# mainboard.net
KiCad netlist of a schematic drawn in EAGLE
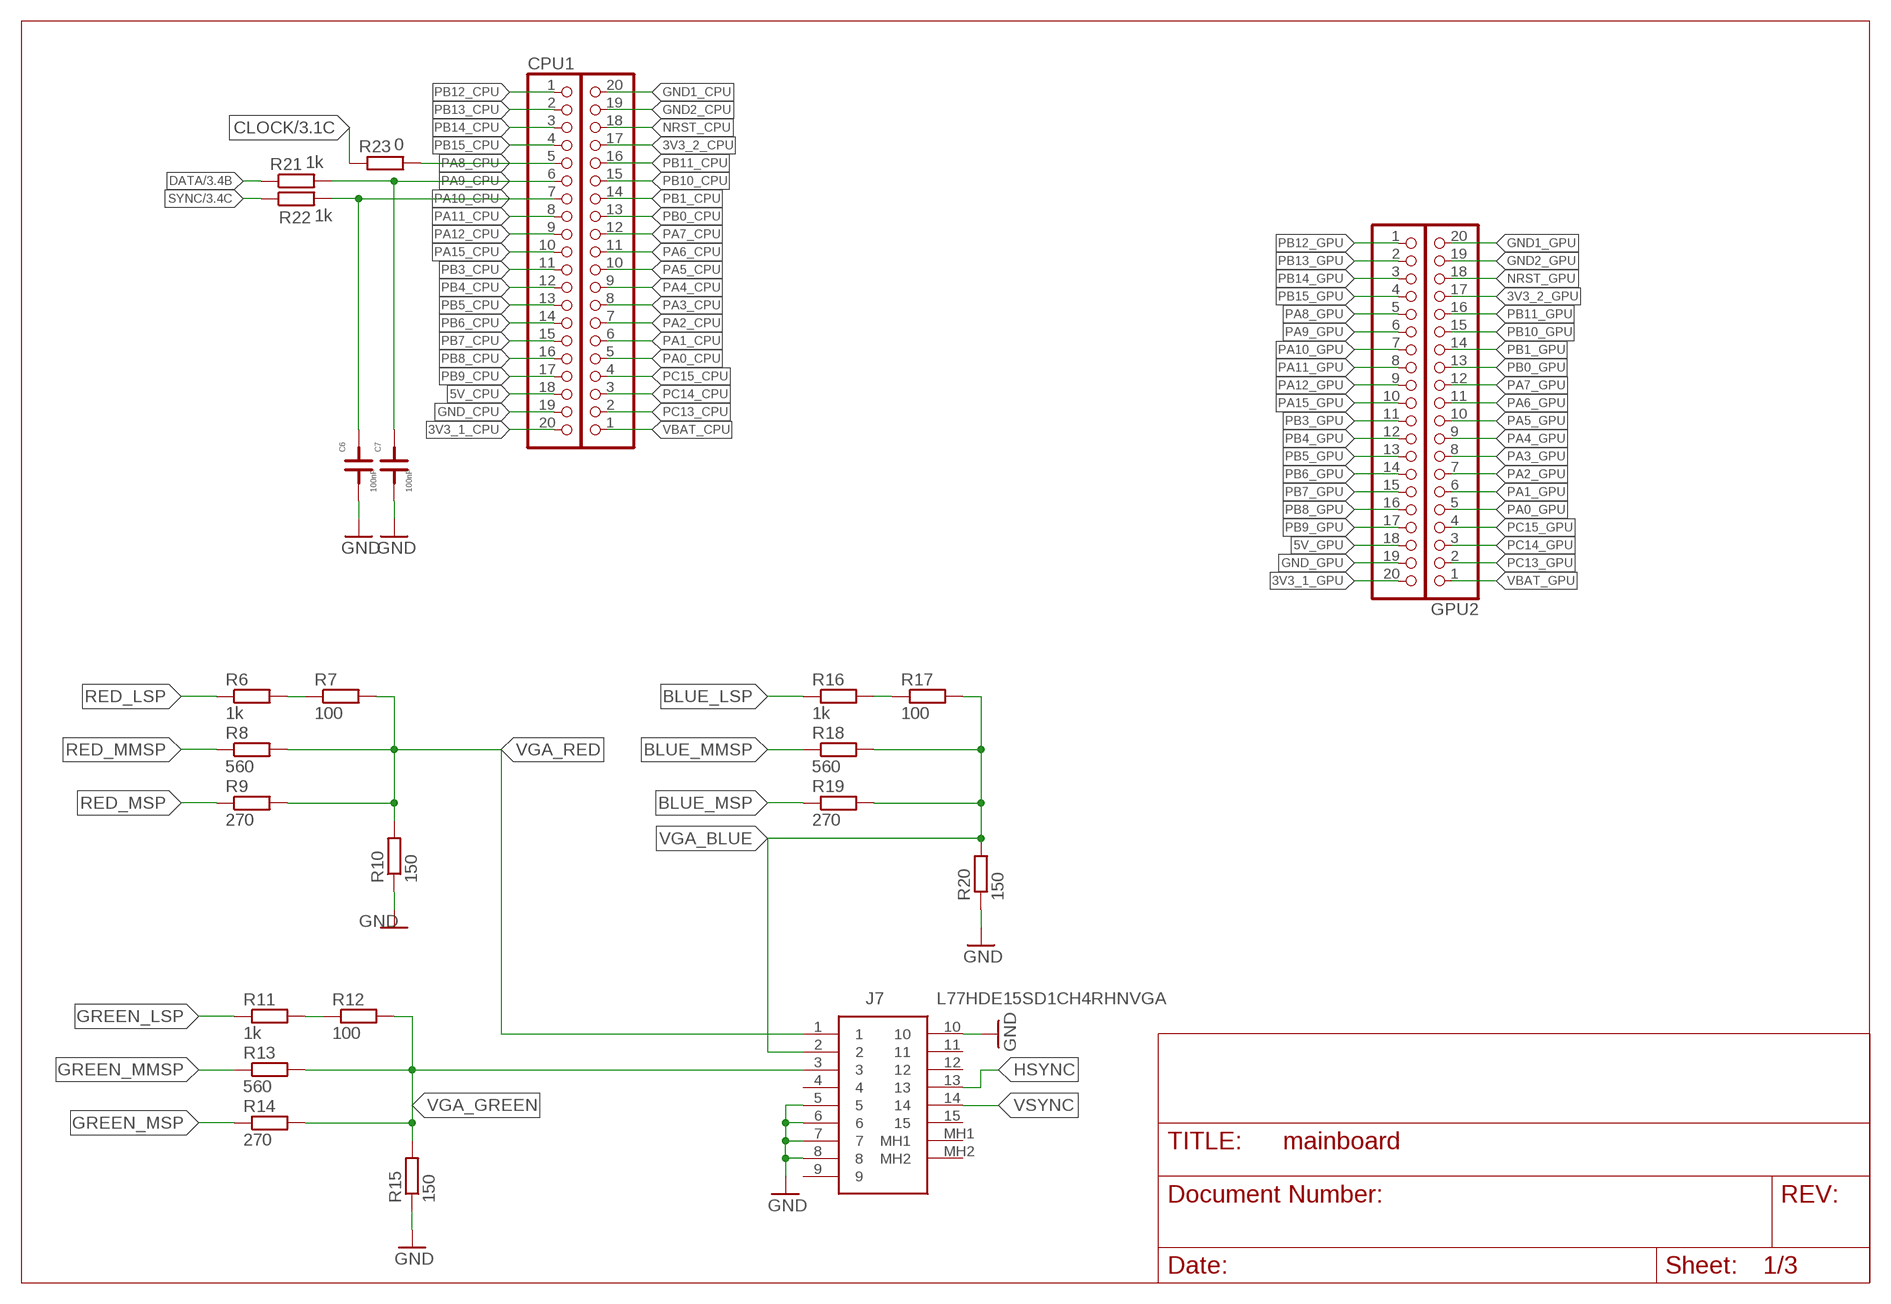
[diagram p0: schematic, sheet 1]
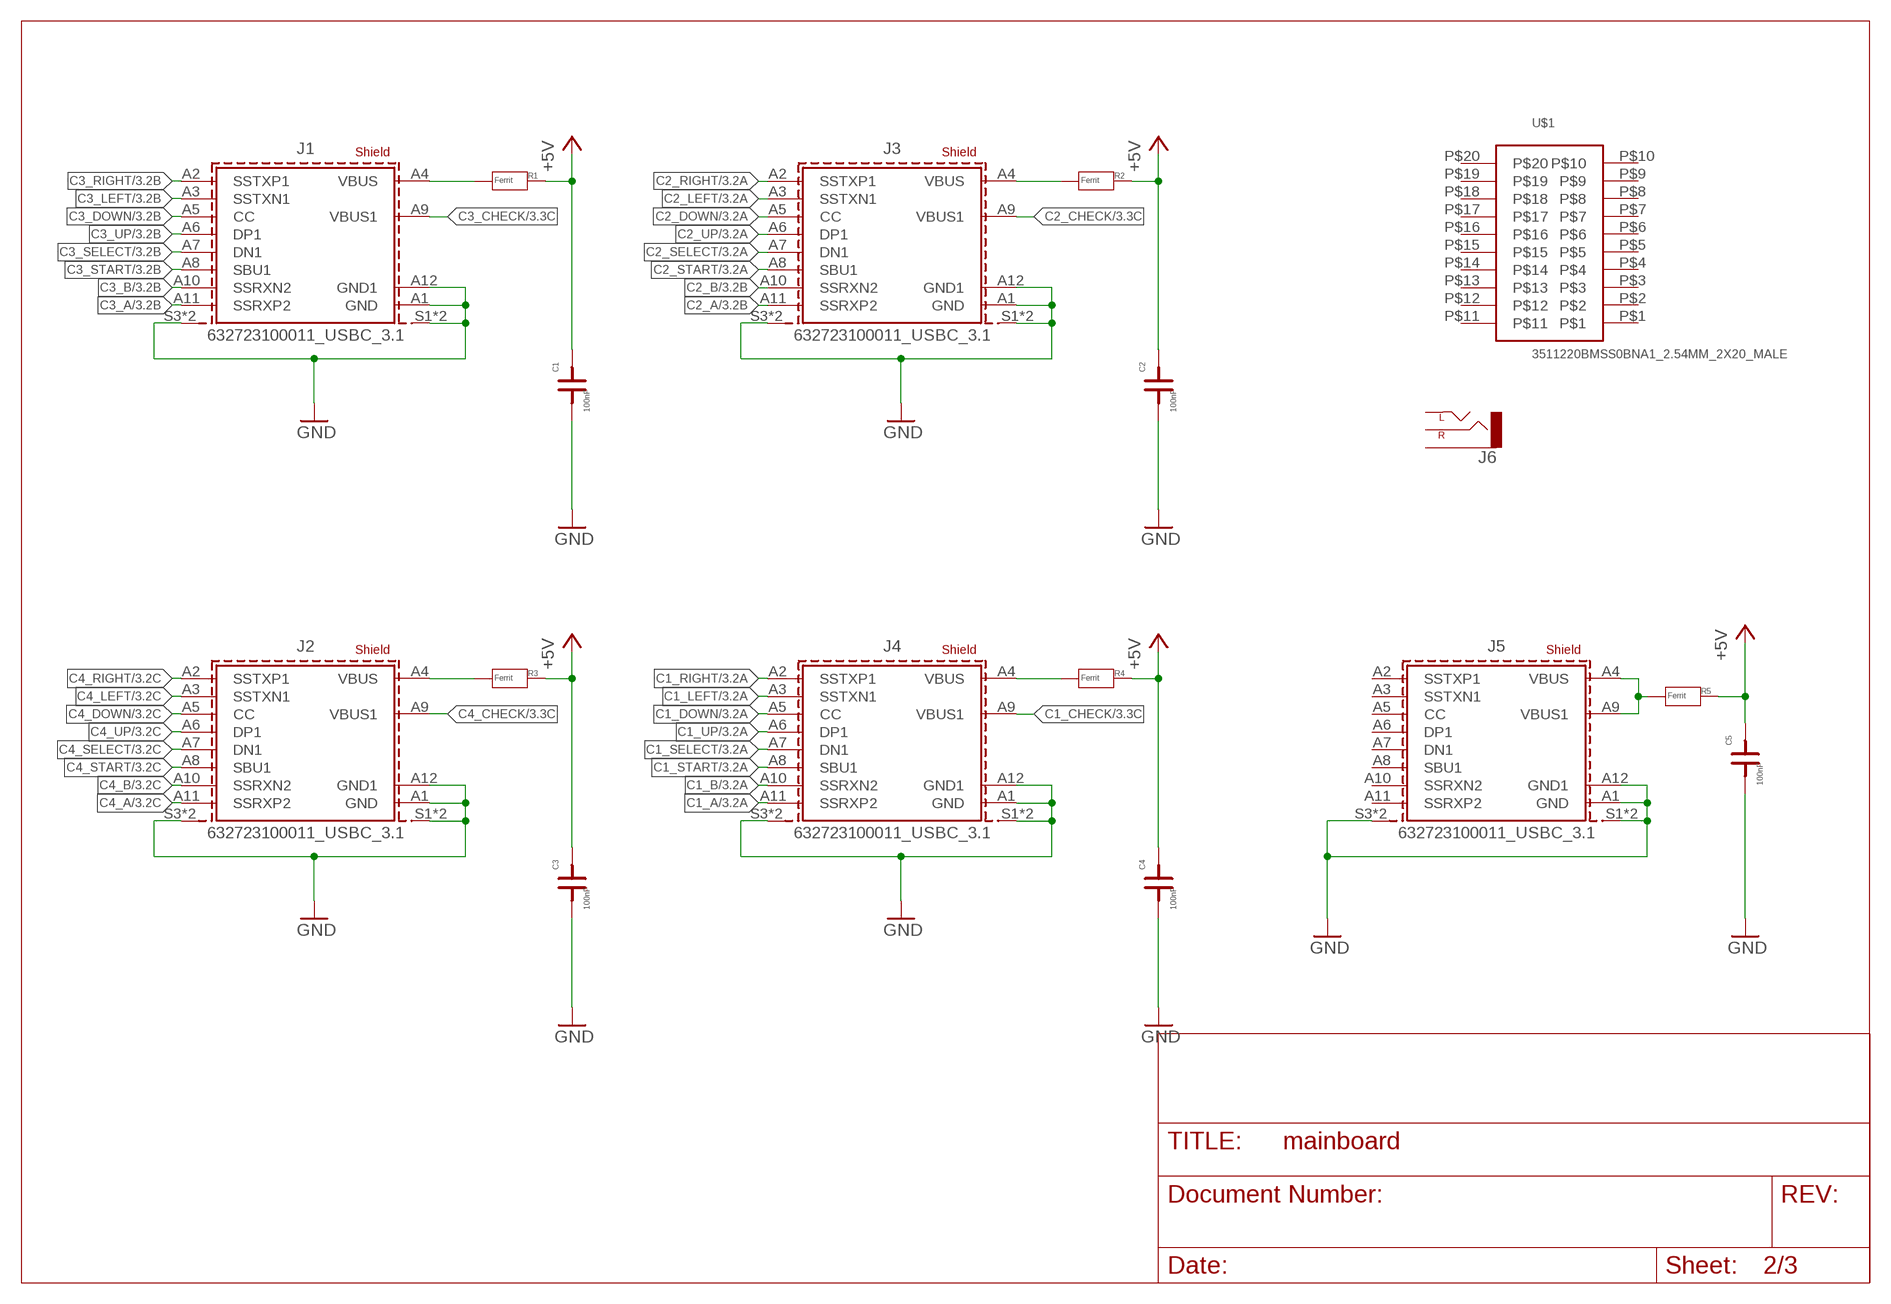
[diagram p1: schematic, sheet 2]
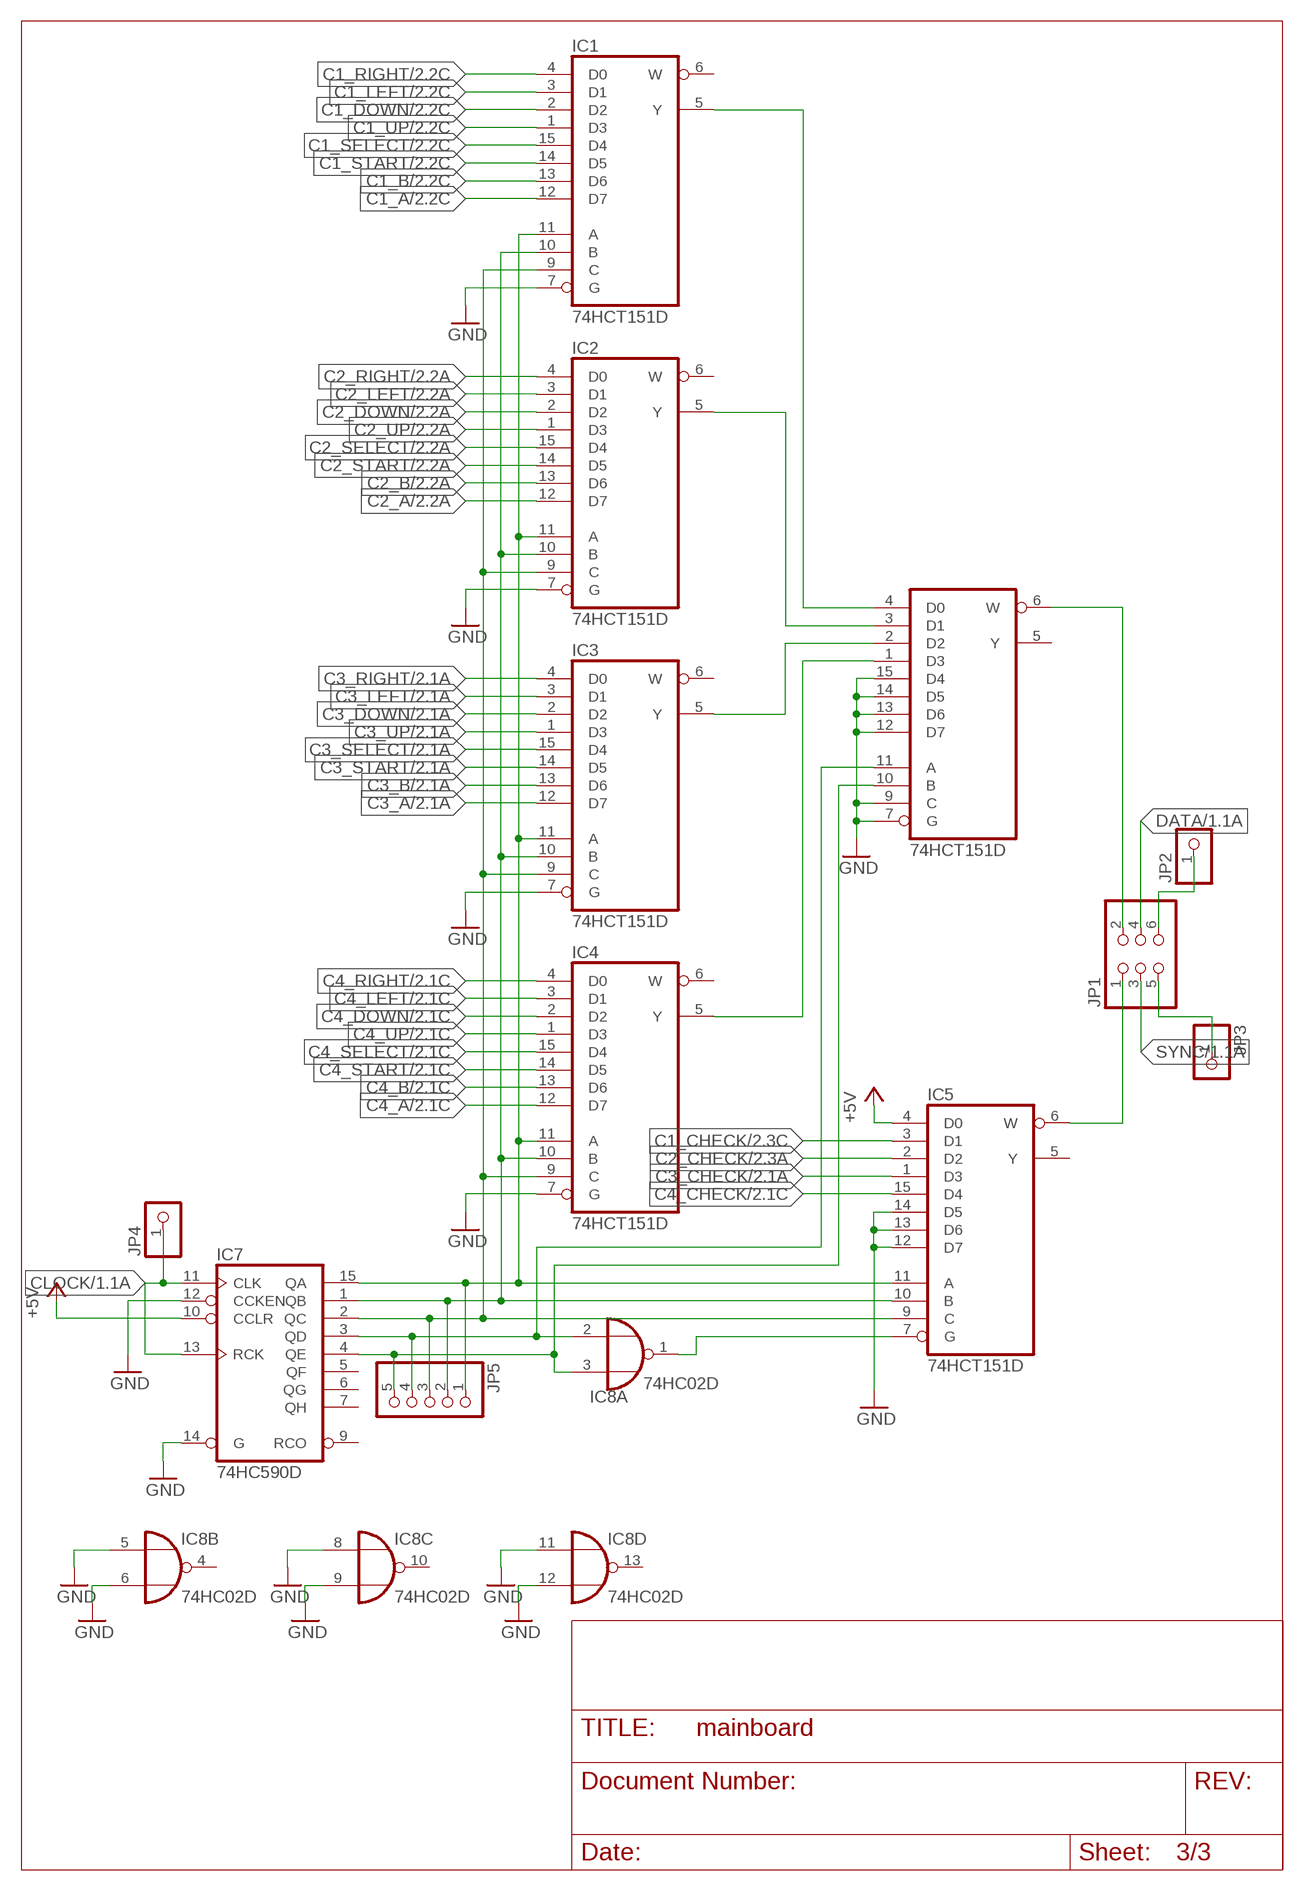
[diagram p2: schematic, sheet 3]

(export (version "E")
  (design (tool "Eeschema 10.0.6"))
  (components
    (comp (ref "C1")
      (value "100nF")
      (footprint "eagle-import:0805F")
      (libsource (lib "eagle-import") (part "C1"))
    )
    (comp (ref "C2")
      (value "100nF")
      (footprint "eagle-import:0805F")
      (libsource (lib "eagle-import") (part "C1"))
    )
    (comp (ref "C3")
      (value "100nF")
      (footprint "eagle-import:0805F")
      (libsource (lib "eagle-import") (part "C1"))
    )
    (comp (ref "C4")
      (value "100nF")
      (footprint "eagle-import:0805F")
      (libsource (lib "eagle-import") (part "C1"))
    )
    (comp (ref "C5")
      (value "100nF")
      (footprint "eagle-import:0805F")
      (libsource (lib "eagle-import") (part "C1"))
    )
    (comp (ref "J1")
      (value "632723100011_USBC_3.1")
      (footprint "eagle-import:632723100011_USBC_3.1")
      (libsource (lib "eagle-import") (part "632723100011_USBC_3.1"))
    )
    (comp (ref "J2")
      (value "632723100011_USBC_3.1")
      (footprint "eagle-import:632723100011_USBC_3.1")
      (libsource (lib "eagle-import") (part "632723100011_USBC_3.1"))
    )
    (comp (ref "J3")
      (value "632723100011_USBC_3.1")
      (footprint "eagle-import:632723100011_USBC_3.1")
      (libsource (lib "eagle-import") (part "632723100011_USBC_3.1"))
    )
    (comp (ref "J4")
      (value "632723100011_USBC_3.1")
      (footprint "eagle-import:632723100011_USBC_3.1")
      (libsource (lib "eagle-import") (part "632723100011_USBC_3.1"))
    )
    (comp (ref "J5")
      (value "632723100011_USBC_3.1")
      (footprint "eagle-import:632723100011_USBC_3.1")
      (libsource (lib "eagle-import") (part "632723100011_USBC_3.1"))
    )
    (comp (ref "J6")
      (value "AUDIO_JACK_2.5MM_2.5MM")
      (footprint "eagle-import:STEREOJACK2.5MM_STEREOJACK2.5MM")
      (libsource (lib "eagle-import") (part "AUDIO_JACK_2.5MM_2.5MM"))
    )
    (comp (ref "R1")
      (value "Ferrit")
      (footprint "eagle-import:1206")
      (libsource (lib "eagle-import") (part "R2"))
    )
    (comp (ref "R2")
      (value "Ferrit")
      (footprint "eagle-import:1206")
      (libsource (lib "eagle-import") (part "R2"))
    )
    (comp (ref "R3")
      (value "Ferrit")
      (footprint "eagle-import:1206")
      (libsource (lib "eagle-import") (part "R2"))
    )
    (comp (ref "R4")
      (value "Ferrit")
      (footprint "eagle-import:1206")
      (libsource (lib "eagle-import") (part "R2"))
    )
    (comp (ref "R5")
      (value "Ferrit")
      (footprint "eagle-import:1206")
      (libsource (lib "eagle-import") (part "R2"))
    )
    (comp (ref "U$1")
      (value "3511220BMSS0BNA1_2.54MM_2X20_MALE")
      (footprint "eagle-import:3511220BMSS0BNA1_2.54MM_2X20_MALE")
      (libsource (lib "eagle-import") (part "3511220BMSS0BNA1_2.54MM_2X20_MALE"))
    )
    (comp (ref "IC1")
      (value "74HCT151D")
      (footprint "eagle-import:SO16")
      (libsource (lib "eagle-import") (part "74151DHCT"))
    )
    (comp (ref "IC2")
      (value "74HCT151D")
      (footprint "eagle-import:SO16")
      (libsource (lib "eagle-import") (part "74151DHCT"))
    )
    (comp (ref "IC3")
      (value "74HCT151D")
      (footprint "eagle-import:SO16")
      (libsource (lib "eagle-import") (part "74151DHCT"))
    )
    (comp (ref "IC4")
      (value "74HCT151D")
      (footprint "eagle-import:SO16")
      (libsource (lib "eagle-import") (part "74151DHCT"))
    )
    (comp (ref "IC5")
      (value "74HCT151D")
      (footprint "eagle-import:SO16")
      (libsource (lib "eagle-import") (part "74151DHCT"))
    )
    (comp (ref "IC6")
      (value "74HCT151D")
      (footprint "eagle-import:SO16")
      (libsource (lib "eagle-import") (part "74151DHCT"))
    )
    (comp (ref "IC7")
      (value "74HC590D")
      (footprint "eagle-import:SO16")
      (libsource (lib "eagle-import") (part "74590DHC"))
    )
    (comp (ref "IC8")
      (value "74HC02D")
      (footprint "eagle-import:SO14")
      (libsource (lib "eagle-import") (part "7402DHC"))
    )
    (comp (ref "JP1")
      (value "PINHD-2X3")
      (footprint "eagle-import:2X03")
      (libsource (lib "eagle-import") (part "PINHD-2X3"))
    )
    (comp (ref "JP2")
      (value "PINHD-1X1")
      (footprint "eagle-import:1X01")
      (libsource (lib "eagle-import") (part "PINHD-1X1"))
    )
    (comp (ref "JP3")
      (value "PINHD-1X1")
      (footprint "eagle-import:1X01")
      (libsource (lib "eagle-import") (part "PINHD-1X1"))
    )
    (comp (ref "JP4")
      (value "PINHD-1X1")
      (footprint "eagle-import:1X01")
      (libsource (lib "eagle-import") (part "PINHD-1X1"))
    )
    (comp (ref "JP5")
      (value "PINHD-1X5")
      (footprint "eagle-import:1X05")
      (libsource (lib "eagle-import") (part "PINHD-1X5"))
    )
    (comp (ref "C6")
      (value "100nF")
      (footprint "eagle-import:0805F")
      (libsource (lib "eagle-import") (part "C1"))
    )
    (comp (ref "C7")
      (value "100nF")
      (footprint "eagle-import:0805F")
      (libsource (lib "eagle-import") (part "C1"))
    )
    (comp (ref "CPU1")
      (value "PINHD-1X20")
      (footprint "eagle-import:1X20")
      (libsource (lib "eagle-import") (part "PINHD-1X20"))
    )
    (comp (ref "CPU2")
      (value "PINHD-1X20")
      (footprint "eagle-import:1X20")
      (libsource (lib "eagle-import") (part "PINHD-1X20"))
    )
    (comp (ref "GPU1")
      (value "PINHD-1X20")
      (footprint "eagle-import:1X20")
      (libsource (lib "eagle-import") (part "PINHD-1X20"))
    )
    (comp (ref "GPU2")
      (value "PINHD-1X20")
      (footprint "eagle-import:1X20")
      (libsource (lib "eagle-import") (part "PINHD-1X20"))
    )
    (comp (ref "J7")
      (value "L77HDE15SD1CH4RHNVGA")
      (footprint "eagle-import:L77HDE15SD1CH4RHNVGA")
      (fields (field (name "MOUSER_PART_NUMBER") "523-7HDE15SDH4RHNVGA"))
      (libsource (lib "eagle-import") (part "L77HDE15SD1CH4RHNVGA"))
    )
    (comp (ref "R6")
      (value "1k")
      (footprint "eagle-import:R0805")
      (libsource (lib "eagle-import") (part "R-EU_R0805"))
    )
    (comp (ref "R7")
      (value "100")
      (footprint "eagle-import:R0805")
      (libsource (lib "eagle-import") (part "R-EU_R0805"))
    )
    (comp (ref "R8")
      (value "560")
      (footprint "eagle-import:R0805")
      (libsource (lib "eagle-import") (part "R-EU_R0805"))
    )
    (comp (ref "R9")
      (value "270")
      (footprint "eagle-import:R0805")
      (libsource (lib "eagle-import") (part "R-EU_R0805"))
    )
    (comp (ref "R10")
      (value "150")
      (footprint "eagle-import:R0805")
      (libsource (lib "eagle-import") (part "R-EU_R0805"))
    )
    (comp (ref "R11")
      (value "1k")
      (footprint "eagle-import:R0805")
      (libsource (lib "eagle-import") (part "R-EU_R0805"))
    )
    (comp (ref "R12")
      (value "100")
      (footprint "eagle-import:R0805")
      (libsource (lib "eagle-import") (part "R-EU_R0805"))
    )
    (comp (ref "R13")
      (value "560")
      (footprint "eagle-import:R0805")
      (libsource (lib "eagle-import") (part "R-EU_R0805"))
    )
    (comp (ref "R14")
      (value "270")
      (footprint "eagle-import:R0805")
      (libsource (lib "eagle-import") (part "R-EU_R0805"))
    )
    (comp (ref "R15")
      (value "150")
      (footprint "eagle-import:R0805")
      (libsource (lib "eagle-import") (part "R-EU_R0805"))
    )
    (comp (ref "R16")
      (value "1k")
      (footprint "eagle-import:R0805")
      (libsource (lib "eagle-import") (part "R-EU_R0805"))
    )
    (comp (ref "R17")
      (value "100")
      (footprint "eagle-import:R0805")
      (libsource (lib "eagle-import") (part "R-EU_R0805"))
    )
    (comp (ref "R18")
      (value "560")
      (footprint "eagle-import:R0805")
      (libsource (lib "eagle-import") (part "R-EU_R0805"))
    )
    (comp (ref "R19")
      (value "270")
      (footprint "eagle-import:R0805")
      (libsource (lib "eagle-import") (part "R-EU_R0805"))
    )
    (comp (ref "R20")
      (value "150")
      (footprint "eagle-import:R0805")
      (libsource (lib "eagle-import") (part "R-EU_R0805"))
    )
    (comp (ref "R21")
      (value "1k")
      (footprint "eagle-import:R0805")
      (libsource (lib "eagle-import") (part "R-EU_R0805"))
    )
    (comp (ref "R22")
      (value "1k")
      (footprint "eagle-import:R0805")
      (libsource (lib "eagle-import") (part "R-EU_R0805"))
    )
    (comp (ref "R23")
      (value "0")
      (footprint "eagle-import:R0805")
      (libsource (lib "eagle-import") (part "R-EU_R0805"))
    )
  )
  (nets
    (net (code "1") (name "+5V") (class "Default")
      (node (ref "C1") (pin "2") (pinfunction "2_2") (pintype "bidirectional"))
      (node (ref "C2") (pin "2") (pinfunction "2_2") (pintype "bidirectional"))
      (node (ref "C3") (pin "2") (pinfunction "2_2") (pintype "bidirectional"))
      (node (ref "C4") (pin "2") (pinfunction "2_2") (pintype "bidirectional"))
      (node (ref "C5") (pin "2") (pinfunction "2_2") (pintype "bidirectional"))
      (node (ref "IC5") (pin "4") (pinfunction "D0_4") (pintype "input"))
      (node (ref "IC7") (pin "10") (pinfunction "CCLR_10") (pintype "input"))
      (node (ref "R1") (pin "2") (pinfunction "2_2") (pintype "bidirectional"))
      (node (ref "R2") (pin "2") (pinfunction "2_2") (pintype "bidirectional"))
      (node (ref "R3") (pin "2") (pinfunction "2_2") (pintype "bidirectional"))
      (node (ref "R4") (pin "2") (pinfunction "2_2") (pintype "bidirectional"))
      (node (ref "R5") (pin "2") (pinfunction "2_2") (pintype "bidirectional"))
    )
    (net (code "2") (name "3V3_1_CPU") (class "Default")
      (node (ref "CPU1") (pin "20") (pinfunction "20_20") (pintype "passive"))
    )
    (net (code "3") (name "3V3_1_GPU") (class "Default")
      (node (ref "GPU1") (pin "20") (pinfunction "20_20") (pintype "passive"))
    )
    (net (code "4") (name "3V3_2_CPU") (class "Default")
      (node (ref "CPU2") (pin "17") (pinfunction "17_17") (pintype "passive"))
    )
    (net (code "5") (name "3V3_2_GPU") (class "Default")
      (node (ref "GPU2") (pin "17") (pinfunction "17_17") (pintype "passive"))
    )
    (net (code "6") (name "5V_CPU") (class "Default")
      (node (ref "CPU1") (pin "18") (pinfunction "18_18") (pintype "passive"))
    )
    (net (code "7") (name "5V_GPU") (class "Default")
      (node (ref "GPU1") (pin "18") (pinfunction "18_18") (pintype "passive"))
    )
    (net (code "8") (name "BLUE_LSP") (class "Default")
      (node (ref "R16") (pin "1") (pinfunction "1_1") (pintype "passive"))
    )
    (net (code "9") (name "BLUE_MMSP") (class "Default")
      (node (ref "R18") (pin "1") (pinfunction "1_1") (pintype "passive"))
    )
    (net (code "10") (name "BLUE_MSP") (class "Default")
      (node (ref "R19") (pin "1") (pinfunction "1_1") (pintype "passive"))
    )
    (net (code "11") (name "C1_A") (class "Default")
      (node (ref "IC1") (pin "12") (pinfunction "D7_12") (pintype "input"))
      (node (ref "J4") (pin "A11") (pinfunction "SSRXP2_A11") (pintype "passive"))
    )
    (net (code "12") (name "C1_B") (class "Default")
      (node (ref "IC1") (pin "13") (pinfunction "D6_13") (pintype "input"))
      (node (ref "J4") (pin "A10") (pinfunction "SSRXN2_A10") (pintype "passive"))
    )
    (net (code "13") (name "C1_CHECK") (class "Default")
      (node (ref "IC5") (pin "3") (pinfunction "D1_3") (pintype "input"))
      (node (ref "J4") (pin "A9") (pinfunction "VBUS1_A9") (pintype "passive"))
    )
    (net (code "14") (name "C1_DOWN") (class "Default")
      (node (ref "IC1") (pin "2") (pinfunction "D2_2") (pintype "input"))
      (node (ref "J4") (pin "A5") (pinfunction "CC_A5") (pintype "passive"))
    )
    (net (code "15") (name "C1_LEFT") (class "Default")
      (node (ref "IC1") (pin "3") (pinfunction "D1_3") (pintype "input"))
      (node (ref "J4") (pin "A3") (pinfunction "SSTXN1_A3") (pintype "passive"))
    )
    (net (code "16") (name "C1_RIGHT") (class "Default")
      (node (ref "IC1") (pin "4") (pinfunction "D0_4") (pintype "input"))
      (node (ref "J4") (pin "A2") (pinfunction "SSTXP1_A2") (pintype "passive"))
    )
    (net (code "17") (name "C1_SELECT") (class "Default")
      (node (ref "IC1") (pin "15") (pinfunction "D4_15") (pintype "input"))
      (node (ref "J4") (pin "A7") (pinfunction "DN1_A7") (pintype "passive"))
    )
    (net (code "18") (name "C1_START") (class "Default")
      (node (ref "IC1") (pin "14") (pinfunction "D5_14") (pintype "input"))
      (node (ref "J4") (pin "A8") (pinfunction "SBU1_A8") (pintype "passive"))
    )
    (net (code "19") (name "C1_UP") (class "Default")
      (node (ref "IC1") (pin "1") (pinfunction "D3_1") (pintype "input"))
      (node (ref "J4") (pin "A6") (pinfunction "DP1_A6") (pintype "passive"))
    )
    (net (code "20") (name "C2_A") (class "Default")
      (node (ref "IC2") (pin "12") (pinfunction "D7_12") (pintype "input"))
      (node (ref "J3") (pin "A11") (pinfunction "SSRXP2_A11") (pintype "passive"))
    )
    (net (code "21") (name "C2_B") (class "Default")
      (node (ref "IC2") (pin "13") (pinfunction "D6_13") (pintype "input"))
      (node (ref "J3") (pin "A10") (pinfunction "SSRXN2_A10") (pintype "passive"))
    )
    (net (code "22") (name "C2_CHECK") (class "Default")
      (node (ref "IC5") (pin "2") (pinfunction "D2_2") (pintype "input"))
      (node (ref "J3") (pin "A9") (pinfunction "VBUS1_A9") (pintype "passive"))
    )
    (net (code "23") (name "C2_DOWN") (class "Default")
      (node (ref "IC2") (pin "2") (pinfunction "D2_2") (pintype "input"))
      (node (ref "J3") (pin "A5") (pinfunction "CC_A5") (pintype "passive"))
    )
    (net (code "24") (name "C2_LEFT") (class "Default")
      (node (ref "IC2") (pin "3") (pinfunction "D1_3") (pintype "input"))
      (node (ref "J3") (pin "A3") (pinfunction "SSTXN1_A3") (pintype "passive"))
    )
    (net (code "25") (name "C2_RIGHT") (class "Default")
      (node (ref "IC2") (pin "4") (pinfunction "D0_4") (pintype "input"))
      (node (ref "J3") (pin "A2") (pinfunction "SSTXP1_A2") (pintype "passive"))
    )
    (net (code "26") (name "C2_SELECT") (class "Default")
      (node (ref "IC2") (pin "15") (pinfunction "D4_15") (pintype "input"))
      (node (ref "J3") (pin "A7") (pinfunction "DN1_A7") (pintype "passive"))
    )
    (net (code "27") (name "C2_START") (class "Default")
      (node (ref "IC2") (pin "14") (pinfunction "D5_14") (pintype "input"))
      (node (ref "J3") (pin "A8") (pinfunction "SBU1_A8") (pintype "passive"))
    )
    (net (code "28") (name "C2_UP") (class "Default")
      (node (ref "IC2") (pin "1") (pinfunction "D3_1") (pintype "input"))
      (node (ref "J3") (pin "A6") (pinfunction "DP1_A6") (pintype "passive"))
    )
    (net (code "29") (name "C3_A") (class "Default")
      (node (ref "IC3") (pin "12") (pinfunction "D7_12") (pintype "input"))
      (node (ref "J1") (pin "A11") (pinfunction "SSRXP2_A11") (pintype "passive"))
    )
    (net (code "30") (name "C3_B") (class "Default")
      (node (ref "IC3") (pin "13") (pinfunction "D6_13") (pintype "input"))
      (node (ref "J1") (pin "A10") (pinfunction "SSRXN2_A10") (pintype "passive"))
    )
    (net (code "31") (name "C3_CHECK") (class "Default")
      (node (ref "IC5") (pin "1") (pinfunction "D3_1") (pintype "input"))
      (node (ref "J1") (pin "A9") (pinfunction "VBUS1_A9") (pintype "passive"))
    )
    (net (code "32") (name "C3_DOWN") (class "Default")
      (node (ref "IC3") (pin "2") (pinfunction "D2_2") (pintype "input"))
      (node (ref "J1") (pin "A5") (pinfunction "CC_A5") (pintype "passive"))
    )
    (net (code "33") (name "C3_LEFT") (class "Default")
      (node (ref "IC3") (pin "3") (pinfunction "D1_3") (pintype "input"))
      (node (ref "J1") (pin "A3") (pinfunction "SSTXN1_A3") (pintype "passive"))
    )
    (net (code "34") (name "C3_RIGHT") (class "Default")
      (node (ref "IC3") (pin "4") (pinfunction "D0_4") (pintype "input"))
      (node (ref "J1") (pin "A2") (pinfunction "SSTXP1_A2") (pintype "passive"))
    )
    (net (code "35") (name "C3_SELECT") (class "Default")
      (node (ref "IC3") (pin "15") (pinfunction "D4_15") (pintype "input"))
      (node (ref "J1") (pin "A7") (pinfunction "DN1_A7") (pintype "passive"))
    )
    (net (code "36") (name "C3_START") (class "Default")
      (node (ref "IC3") (pin "14") (pinfunction "D5_14") (pintype "input"))
      (node (ref "J1") (pin "A8") (pinfunction "SBU1_A8") (pintype "passive"))
    )
    (net (code "37") (name "C3_UP") (class "Default")
      (node (ref "IC3") (pin "1") (pinfunction "D3_1") (pintype "input"))
      (node (ref "J1") (pin "A6") (pinfunction "DP1_A6") (pintype "passive"))
    )
    (net (code "38") (name "C4_A") (class "Default")
      (node (ref "IC4") (pin "12") (pinfunction "D7_12") (pintype "input"))
      (node (ref "J2") (pin "A11") (pinfunction "SSRXP2_A11") (pintype "passive"))
    )
    (net (code "39") (name "C4_B") (class "Default")
      (node (ref "IC4") (pin "13") (pinfunction "D6_13") (pintype "input"))
      (node (ref "J2") (pin "A10") (pinfunction "SSRXN2_A10") (pintype "passive"))
    )
    (net (code "40") (name "C4_CHECK") (class "Default")
      (node (ref "IC5") (pin "15") (pinfunction "D4_15") (pintype "input"))
      (node (ref "J2") (pin "A9") (pinfunction "VBUS1_A9") (pintype "passive"))
    )
    (net (code "41") (name "C4_DOWN") (class "Default")
      (node (ref "IC4") (pin "2") (pinfunction "D2_2") (pintype "input"))
      (node (ref "J2") (pin "A5") (pinfunction "CC_A5") (pintype "passive"))
    )
    (net (code "42") (name "C4_LEFT") (class "Default")
      (node (ref "IC4") (pin "3") (pinfunction "D1_3") (pintype "input"))
      (node (ref "J2") (pin "A3") (pinfunction "SSTXN1_A3") (pintype "passive"))
    )
    (net (code "43") (name "C4_RIGHT") (class "Default")
      (node (ref "IC4") (pin "4") (pinfunction "D0_4") (pintype "input"))
      (node (ref "J2") (pin "A2") (pinfunction "SSTXP1_A2") (pintype "passive"))
    )
    (net (code "44") (name "C4_SELECT") (class "Default")
      (node (ref "IC4") (pin "15") (pinfunction "D4_15") (pintype "input"))
      (node (ref "J2") (pin "A7") (pinfunction "DN1_A7") (pintype "passive"))
    )
    (net (code "45") (name "C4_START") (class "Default")
      (node (ref "IC4") (pin "14") (pinfunction "D5_14") (pintype "input"))
      (node (ref "J2") (pin "A8") (pinfunction "SBU1_A8") (pintype "passive"))
    )
    (net (code "46") (name "C4_UP") (class "Default")
      (node (ref "IC4") (pin "1") (pinfunction "D3_1") (pintype "input"))
      (node (ref "J2") (pin "A6") (pinfunction "DP1_A6") (pintype "passive"))
    )
    (net (code "47") (name "CLOCK") (class "Default")
      (node (ref "IC7") (pin "11") (pinfunction "CLK_11") (pintype "input"))
      (node (ref "IC7") (pin "13") (pinfunction "RCK_13") (pintype "input"))
      (node (ref "JP4") (pin "1") (pinfunction "1_1") (pintype "passive"))
      (node (ref "R23") (pin "1") (pinfunction "1_1") (pintype "passive"))
    )
    (net (code "48") (name "DATA") (class "Default")
      (node (ref "JP1") (pin "4") (pinfunction "4_4") (pintype "passive"))
      (node (ref "R21") (pin "1") (pinfunction "1_1") (pintype "passive"))
    )
    (net (code "49") (name "GND") (class "Default")
      (node (ref "C1") (pin "1") (pinfunction "1_1") (pintype "bidirectional"))
      (node (ref "C2") (pin "1") (pinfunction "1_1") (pintype "bidirectional"))
      (node (ref "C3") (pin "1") (pinfunction "1_1") (pintype "bidirectional"))
      (node (ref "C4") (pin "1") (pinfunction "1_1") (pintype "bidirectional"))
      (node (ref "C5") (pin "1") (pinfunction "1_1") (pintype "bidirectional"))
      (node (ref "C6") (pin "1") (pinfunction "1_1") (pintype "bidirectional"))
      (node (ref "C7") (pin "1") (pinfunction "1_1") (pintype "bidirectional"))
      (node (ref "IC1") (pin "7") (pinfunction "G_7") (pintype "input"))
      (node (ref "IC2") (pin "7") (pinfunction "G_7") (pintype "input"))
      (node (ref "IC3") (pin "7") (pinfunction "G_7") (pintype "input"))
      (node (ref "IC4") (pin "7") (pinfunction "G_7") (pintype "input"))
      (node (ref "IC5") (pin "12") (pinfunction "D7_12") (pintype "input"))
      (node (ref "IC5") (pin "13") (pinfunction "D6_13") (pintype "input"))
      (node (ref "IC5") (pin "14") (pinfunction "D5_14") (pintype "input"))
      (node (ref "IC6") (pin "12") (pinfunction "D7_12") (pintype "input"))
      (node (ref "IC6") (pin "13") (pinfunction "D6_13") (pintype "input"))
      (node (ref "IC6") (pin "14") (pinfunction "D5_14") (pintype "input"))
      (node (ref "IC6") (pin "15") (pinfunction "D4_15") (pintype "input"))
      (node (ref "IC6") (pin "7") (pinfunction "G_7") (pintype "input"))
      (node (ref "IC6") (pin "9") (pinfunction "C_9") (pintype "input"))
      (node (ref "IC7") (pin "12") (pinfunction "CCKEN_12") (pintype "input"))
      (node (ref "IC7") (pin "14") (pinfunction "G_14") (pintype "input"))
      (node (ref "IC8") (pin "11") (pinfunction "I0_11") (pintype "input"))
      (node (ref "IC8") (pin "12") (pinfunction "I1_12") (pintype "input"))
      (node (ref "IC8") (pin "5") (pinfunction "I0_5") (pintype "input"))
      (node (ref "IC8") (pin "6") (pinfunction "I1_6") (pintype "input"))
      (node (ref "IC8") (pin "8") (pinfunction "I0_8") (pintype "input"))
      (node (ref "IC8") (pin "9") (pinfunction "I1_9") (pintype "input"))
      (node (ref "J1") (pin "A1") (pinfunction "GND_A1") (pintype "passive"))
      (node (ref "J1") (pin "A12") (pinfunction "GND1_A12") (pintype "passive"))
      (node (ref "J1") (pin "S1") (pinfunction "SHIELD1_S1") (pintype "passive"))
      (node (ref "J1") (pin "S2") (pinfunction "SHIELD1_S2") (pintype "passive"))
      (node (ref "J1") (pin "S3") (pinfunction "SHIELD_S3") (pintype "passive"))
      (node (ref "J1") (pin "S4") (pinfunction "SHIELD_S4") (pintype "passive"))
      (node (ref "J2") (pin "A1") (pinfunction "GND_A1") (pintype "passive"))
      (node (ref "J2") (pin "A12") (pinfunction "GND1_A12") (pintype "passive"))
      (node (ref "J2") (pin "S1") (pinfunction "SHIELD1_S1") (pintype "passive"))
      (node (ref "J2") (pin "S2") (pinfunction "SHIELD1_S2") (pintype "passive"))
      (node (ref "J2") (pin "S3") (pinfunction "SHIELD_S3") (pintype "passive"))
      (node (ref "J2") (pin "S4") (pinfunction "SHIELD_S4") (pintype "passive"))
      (node (ref "J3") (pin "A1") (pinfunction "GND_A1") (pintype "passive"))
      (node (ref "J3") (pin "A12") (pinfunction "GND1_A12") (pintype "passive"))
      (node (ref "J3") (pin "S1") (pinfunction "SHIELD1_S1") (pintype "passive"))
      (node (ref "J3") (pin "S2") (pinfunction "SHIELD1_S2") (pintype "passive"))
      (node (ref "J3") (pin "S3") (pinfunction "SHIELD_S3") (pintype "passive"))
      (node (ref "J3") (pin "S4") (pinfunction "SHIELD_S4") (pintype "passive"))
      (node (ref "J4") (pin "A1") (pinfunction "GND_A1") (pintype "passive"))
      (node (ref "J4") (pin "A12") (pinfunction "GND1_A12") (pintype "passive"))
      (node (ref "J4") (pin "S1") (pinfunction "SHIELD1_S1") (pintype "passive"))
      (node (ref "J4") (pin "S2") (pinfunction "SHIELD1_S2") (pintype "passive"))
      (node (ref "J4") (pin "S3") (pinfunction "SHIELD_S3") (pintype "passive"))
      (node (ref "J4") (pin "S4") (pinfunction "SHIELD_S4") (pintype "passive"))
      (node (ref "J5") (pin "A1") (pinfunction "GND_A1") (pintype "passive"))
      (node (ref "J5") (pin "A12") (pinfunction "GND1_A12") (pintype "passive"))
      (node (ref "J5") (pin "S1") (pinfunction "SHIELD1_S1") (pintype "passive"))
      (node (ref "J5") (pin "S2") (pinfunction "SHIELD1_S2") (pintype "passive"))
      (node (ref "J5") (pin "S3") (pinfunction "SHIELD_S3") (pintype "passive"))
      (node (ref "J5") (pin "S4") (pinfunction "SHIELD_S4") (pintype "passive"))
      (node (ref "J7") (pin "10") (pinfunction "10_10") (pintype "bidirectional"))
      (node (ref "J7") (pin "5") (pinfunction "5_5") (pintype "bidirectional"))
      (node (ref "J7") (pin "6") (pinfunction "6_6") (pintype "bidirectional"))
      (node (ref "J7") (pin "7") (pinfunction "7_7") (pintype "bidirectional"))
      (node (ref "J7") (pin "8") (pinfunction "8_8") (pintype "bidirectional"))
      (node (ref "R10") (pin "1") (pinfunction "1_1") (pintype "passive"))
      (node (ref "R15") (pin "1") (pinfunction "1_1") (pintype "passive"))
      (node (ref "R20") (pin "1") (pinfunction "1_1") (pintype "passive"))
    )
    (net (code "50") (name "GND1_CPU") (class "Default")
      (node (ref "CPU2") (pin "20") (pinfunction "20_20") (pintype "passive"))
    )
    (net (code "51") (name "GND1_GPU") (class "Default")
      (node (ref "GPU2") (pin "20") (pinfunction "20_20") (pintype "passive"))
    )
    (net (code "52") (name "GND2_CPU") (class "Default")
      (node (ref "CPU2") (pin "19") (pinfunction "19_19") (pintype "passive"))
    )
    (net (code "53") (name "GND2_GPU") (class "Default")
      (node (ref "GPU2") (pin "19") (pinfunction "19_19") (pintype "passive"))
    )
    (net (code "54") (name "GND_CPU") (class "Default")
      (node (ref "CPU1") (pin "19") (pinfunction "19_19") (pintype "passive"))
    )
    (net (code "55") (name "GND_GPU") (class "Default")
      (node (ref "GPU1") (pin "19") (pinfunction "19_19") (pintype "passive"))
    )
    (net (code "56") (name "GREEN_LSP") (class "Default")
      (node (ref "R11") (pin "1") (pinfunction "1_1") (pintype "passive"))
    )
    (net (code "57") (name "GREEN_MMSP") (class "Default")
      (node (ref "R13") (pin "1") (pinfunction "1_1") (pintype "passive"))
    )
    (net (code "58") (name "GREEN_MSP") (class "Default")
      (node (ref "R14") (pin "1") (pinfunction "1_1") (pintype "passive"))
    )
    (net (code "59") (name "HSYNC") (class "Default")
      (node (ref "J7") (pin "13") (pinfunction "13_13") (pintype "bidirectional"))
    )
    (net (code "60") (name "NRST_CPU") (class "Default")
      (node (ref "CPU2") (pin "18") (pinfunction "18_18") (pintype "passive"))
    )
    (net (code "61") (name "NRST_GPU") (class "Default")
      (node (ref "GPU2") (pin "18") (pinfunction "18_18") (pintype "passive"))
    )
    (net (code "62") (name "Net-(IC1A-A)") (class "Default")
      (node (ref "IC1") (pin "11") (pinfunction "A_11") (pintype "input"))
      (node (ref "IC2") (pin "11") (pinfunction "A_11") (pintype "input"))
      (node (ref "IC3") (pin "11") (pinfunction "A_11") (pintype "input"))
      (node (ref "IC4") (pin "11") (pinfunction "A_11") (pintype "input"))
      (node (ref "IC5") (pin "11") (pinfunction "A_11") (pintype "input"))
      (node (ref "IC7") (pin "15") (pinfunction "QA_15") (pintype "tri_state"))
      (node (ref "JP5") (pin "1") (pinfunction "1_1") (pintype "passive"))
    )
    (net (code "63") (name "Net-(IC1A-B)") (class "Default")
      (node (ref "IC1") (pin "10") (pinfunction "B_10") (pintype "input"))
      (node (ref "IC2") (pin "10") (pinfunction "B_10") (pintype "input"))
      (node (ref "IC3") (pin "10") (pinfunction "B_10") (pintype "input"))
      (node (ref "IC4") (pin "10") (pinfunction "B_10") (pintype "input"))
      (node (ref "IC5") (pin "10") (pinfunction "B_10") (pintype "input"))
      (node (ref "IC7") (pin "1") (pinfunction "QB_1") (pintype "tri_state"))
      (node (ref "JP5") (pin "2") (pinfunction "2_2") (pintype "passive"))
    )
    (net (code "64") (name "Net-(IC1A-C)") (class "Default")
      (node (ref "IC1") (pin "9") (pinfunction "C_9") (pintype "input"))
      (node (ref "IC2") (pin "9") (pinfunction "C_9") (pintype "input"))
      (node (ref "IC3") (pin "9") (pinfunction "C_9") (pintype "input"))
      (node (ref "IC4") (pin "9") (pinfunction "C_9") (pintype "input"))
      (node (ref "IC5") (pin "9") (pinfunction "C_9") (pintype "input"))
      (node (ref "IC7") (pin "2") (pinfunction "QC_2") (pintype "tri_state"))
      (node (ref "JP5") (pin "3") (pinfunction "3_3") (pintype "passive"))
    )
    (net (code "65") (name "Net-(IC1A-Y)") (class "Default")
      (node (ref "IC1") (pin "5") (pinfunction "Y_5") (pintype "output"))
      (node (ref "IC6") (pin "4") (pinfunction "D0_4") (pintype "input"))
    )
    (net (code "66") (name "Net-(IC2A-Y)") (class "Default")
      (node (ref "IC2") (pin "5") (pinfunction "Y_5") (pintype "output"))
      (node (ref "IC6") (pin "3") (pinfunction "D1_3") (pintype "input"))
    )
    (net (code "67") (name "Net-(IC3A-Y)") (class "Default")
      (node (ref "IC3") (pin "5") (pinfunction "Y_5") (pintype "output"))
      (node (ref "IC6") (pin "2") (pinfunction "D2_2") (pintype "input"))
    )
    (net (code "68") (name "Net-(IC4A-Y)") (class "Default")
      (node (ref "IC4") (pin "5") (pinfunction "Y_5") (pintype "output"))
      (node (ref "IC6") (pin "1") (pinfunction "D3_1") (pintype "input"))
    )
    (net (code "69") (name "Net-(IC5A-G)") (class "Default")
      (node (ref "IC5") (pin "7") (pinfunction "G_7") (pintype "input"))
      (node (ref "IC8") (pin "1") (pinfunction "O_1") (pintype "output"))
    )
    (net (code "70") (name "Net-(IC5A-W)") (class "Default")
      (node (ref "IC5") (pin "6") (pinfunction "W_6") (pintype "output"))
      (node (ref "JP1") (pin "1") (pinfunction "1_1") (pintype "passive"))
    )
    (net (code "71") (name "Net-(IC6A-A)") (class "Default")
      (node (ref "IC6") (pin "11") (pinfunction "A_11") (pintype "input"))
      (node (ref "IC7") (pin "3") (pinfunction "QD_3") (pintype "tri_state"))
      (node (ref "IC8") (pin "2") (pinfunction "I0_2") (pintype "input"))
      (node (ref "JP5") (pin "4") (pinfunction "4_4") (pintype "passive"))
    )
    (net (code "72") (name "Net-(IC6A-B)") (class "Default")
      (node (ref "IC6") (pin "10") (pinfunction "B_10") (pintype "input"))
      (node (ref "IC7") (pin "4") (pinfunction "QE_4") (pintype "tri_state"))
      (node (ref "IC8") (pin "3") (pinfunction "I1_3") (pintype "input"))
      (node (ref "JP5") (pin "5") (pinfunction "5_5") (pintype "passive"))
    )
    (net (code "73") (name "Net-(IC6A-W)") (class "Default")
      (node (ref "IC6") (pin "6") (pinfunction "W_6") (pintype "output"))
      (node (ref "JP1") (pin "2") (pinfunction "2_2") (pintype "passive"))
    )
    (net (code "74") (name "Net-(J1-VBUS)") (class "Default")
      (node (ref "J1") (pin "A4") (pinfunction "VBUS_A4") (pintype "passive"))
      (node (ref "R1") (pin "1") (pinfunction "1_1") (pintype "bidirectional"))
    )
    (net (code "75") (name "Net-(J2-VBUS)") (class "Default")
      (node (ref "J2") (pin "A4") (pinfunction "VBUS_A4") (pintype "passive"))
      (node (ref "R3") (pin "1") (pinfunction "1_1") (pintype "bidirectional"))
    )
    (net (code "76") (name "Net-(J3-VBUS)") (class "Default")
      (node (ref "J3") (pin "A4") (pinfunction "VBUS_A4") (pintype "passive"))
      (node (ref "R2") (pin "1") (pinfunction "1_1") (pintype "bidirectional"))
    )
    (net (code "77") (name "Net-(J4-VBUS)") (class "Default")
      (node (ref "J4") (pin "A4") (pinfunction "VBUS_A4") (pintype "passive"))
      (node (ref "R4") (pin "1") (pinfunction "1_1") (pintype "bidirectional"))
    )
    (net (code "78") (name "Net-(J5-VBUS)") (class "Default")
      (node (ref "J5") (pin "A4") (pinfunction "VBUS_A4") (pintype "passive"))
      (node (ref "J5") (pin "A9") (pinfunction "VBUS1_A9") (pintype "passive"))
      (node (ref "R5") (pin "1") (pinfunction "1_1") (pintype "bidirectional"))
    )
    (net (code "79") (name "Net-(JP1-Pad5)") (class "Default")
      (node (ref "JP1") (pin "5") (pinfunction "5_5") (pintype "passive"))
      (node (ref "JP3") (pin "1") (pinfunction "1_1") (pintype "passive"))
    )
    (net (code "80") (name "Net-(JP1-Pad6)") (class "Default")
      (node (ref "JP1") (pin "6") (pinfunction "6_6") (pintype "passive"))
      (node (ref "JP2") (pin "1") (pinfunction "1_1") (pintype "passive"))
    )
    (net (code "81") (name "Net-(R6-Pad2)") (class "Default")
      (node (ref "R6") (pin "2") (pinfunction "2_2") (pintype "passive"))
      (node (ref "R7") (pin "1") (pinfunction "1_1") (pintype "passive"))
    )
    (net (code "82") (name "Net-(R11-Pad2)") (class "Default")
      (node (ref "R11") (pin "2") (pinfunction "2_2") (pintype "passive"))
      (node (ref "R12") (pin "1") (pinfunction "1_1") (pintype "passive"))
    )
    (net (code "83") (name "Net-(R16-Pad2)") (class "Default")
      (node (ref "R16") (pin "2") (pinfunction "2_2") (pintype "passive"))
      (node (ref "R17") (pin "1") (pinfunction "1_1") (pintype "passive"))
    )
    (net (code "84") (name "PA0_CPU") (class "Default")
      (node (ref "CPU2") (pin "5") (pinfunction "5_5") (pintype "passive"))
    )
    (net (code "85") (name "PA0_GPU") (class "Default")
      (node (ref "GPU2") (pin "5") (pinfunction "5_5") (pintype "passive"))
    )
    (net (code "86") (name "PA1_CPU") (class "Default")
      (node (ref "CPU2") (pin "6") (pinfunction "6_6") (pintype "passive"))
    )
    (net (code "87") (name "PA1_GPU") (class "Default")
      (node (ref "GPU2") (pin "6") (pinfunction "6_6") (pintype "passive"))
    )
    (net (code "88") (name "PA2_CPU") (class "Default")
      (node (ref "CPU2") (pin "7") (pinfunction "7_7") (pintype "passive"))
    )
    (net (code "89") (name "PA2_GPU") (class "Default")
      (node (ref "GPU2") (pin "7") (pinfunction "7_7") (pintype "passive"))
    )
    (net (code "90") (name "PA3_CPU") (class "Default")
      (node (ref "CPU2") (pin "8") (pinfunction "8_8") (pintype "passive"))
    )
    (net (code "91") (name "PA3_GPU") (class "Default")
      (node (ref "GPU2") (pin "8") (pinfunction "8_8") (pintype "passive"))
    )
    (net (code "92") (name "PA4_CPU") (class "Default")
      (node (ref "CPU2") (pin "9") (pinfunction "9_9") (pintype "passive"))
    )
    (net (code "93") (name "PA4_GPU") (class "Default")
      (node (ref "GPU2") (pin "9") (pinfunction "9_9") (pintype "passive"))
    )
    (net (code "94") (name "PA5_CPU") (class "Default")
      (node (ref "CPU2") (pin "10") (pinfunction "10_10") (pintype "passive"))
    )
    (net (code "95") (name "PA5_GPU") (class "Default")
      (node (ref "GPU2") (pin "10") (pinfunction "10_10") (pintype "passive"))
    )
    (net (code "96") (name "PA6_CPU") (class "Default")
      (node (ref "CPU2") (pin "11") (pinfunction "11_11") (pintype "passive"))
    )
    (net (code "97") (name "PA6_GPU") (class "Default")
      (node (ref "GPU2") (pin "11") (pinfunction "11_11") (pintype "passive"))
    )
    (net (code "98") (name "PA7_CPU") (class "Default")
      (node (ref "CPU2") (pin "12") (pinfunction "12_12") (pintype "passive"))
    )
    (net (code "99") (name "PA7_GPU") (class "Default")
      (node (ref "GPU2") (pin "12") (pinfunction "12_12") (pintype "passive"))
    )
    (net (code "100") (name "PA8_CPU") (class "Default")
      (node (ref "CPU1") (pin "5") (pinfunction "5_5") (pintype "passive"))
      (node (ref "R23") (pin "2") (pinfunction "2_2") (pintype "passive"))
    )
    (net (code "101") (name "PA8_GPU") (class "Default")
      (node (ref "GPU1") (pin "5") (pinfunction "5_5") (pintype "passive"))
    )
    (net (code "102") (name "PA9_CPU") (class "Default")
      (node (ref "C7") (pin "2") (pinfunction "2_2") (pintype "bidirectional"))
      (node (ref "CPU1") (pin "6") (pinfunction "6_6") (pintype "passive"))
      (node (ref "R21") (pin "2") (pinfunction "2_2") (pintype "passive"))
    )
    (net (code "103") (name "PA9_GPU") (class "Default")
      (node (ref "GPU1") (pin "6") (pinfunction "6_6") (pintype "passive"))
    )
    (net (code "104") (name "PA10_CPU") (class "Default")
      (node (ref "C6") (pin "2") (pinfunction "2_2") (pintype "bidirectional"))
      (node (ref "CPU1") (pin "7") (pinfunction "7_7") (pintype "passive"))
      (node (ref "R22") (pin "2") (pinfunction "2_2") (pintype "passive"))
    )
    (net (code "105") (name "PA10_GPU") (class "Default")
      (node (ref "GPU1") (pin "7") (pinfunction "7_7") (pintype "passive"))
    )
    (net (code "106") (name "PA11_CPU") (class "Default")
      (node (ref "CPU1") (pin "8") (pinfunction "8_8") (pintype "passive"))
    )
    (net (code "107") (name "PA11_GPU") (class "Default")
      (node (ref "GPU1") (pin "8") (pinfunction "8_8") (pintype "passive"))
    )
    (net (code "108") (name "PA12_CPU") (class "Default")
      (node (ref "CPU1") (pin "9") (pinfunction "9_9") (pintype "passive"))
    )
    (net (code "109") (name "PA12_GPU") (class "Default")
      (node (ref "GPU1") (pin "9") (pinfunction "9_9") (pintype "passive"))
    )
    (net (code "110") (name "PA15_CPU") (class "Default")
      (node (ref "CPU1") (pin "10") (pinfunction "10_10") (pintype "passive"))
    )
    (net (code "111") (name "PA15_GPU") (class "Default")
      (node (ref "GPU1") (pin "10") (pinfunction "10_10") (pintype "passive"))
    )
    (net (code "112") (name "PB0_CPU") (class "Default")
      (node (ref "CPU2") (pin "13") (pinfunction "13_13") (pintype "passive"))
    )
    (net (code "113") (name "PB0_GPU") (class "Default")
      (node (ref "GPU2") (pin "13") (pinfunction "13_13") (pintype "passive"))
    )
    (net (code "114") (name "PB1_CPU") (class "Default")
      (node (ref "CPU2") (pin "14") (pinfunction "14_14") (pintype "passive"))
    )
    (net (code "115") (name "PB1_GPU") (class "Default")
      (node (ref "GPU2") (pin "14") (pinfunction "14_14") (pintype "passive"))
    )
    (net (code "116") (name "PB3_CPU") (class "Default")
      (node (ref "CPU1") (pin "11") (pinfunction "11_11") (pintype "passive"))
    )
    (net (code "117") (name "PB3_GPU") (class "Default")
      (node (ref "GPU1") (pin "11") (pinfunction "11_11") (pintype "passive"))
    )
    (net (code "118") (name "PB4_CPU") (class "Default")
      (node (ref "CPU1") (pin "12") (pinfunction "12_12") (pintype "passive"))
    )
    (net (code "119") (name "PB4_GPU") (class "Default")
      (node (ref "GPU1") (pin "12") (pinfunction "12_12") (pintype "passive"))
    )
    (net (code "120") (name "PB5_CPU") (class "Default")
      (node (ref "CPU1") (pin "13") (pinfunction "13_13") (pintype "passive"))
    )
    (net (code "121") (name "PB5_GPU") (class "Default")
      (node (ref "GPU1") (pin "13") (pinfunction "13_13") (pintype "passive"))
    )
    (net (code "122") (name "PB6_CPU") (class "Default")
      (node (ref "CPU1") (pin "14") (pinfunction "14_14") (pintype "passive"))
    )
    (net (code "123") (name "PB6_GPU") (class "Default")
      (node (ref "GPU1") (pin "14") (pinfunction "14_14") (pintype "passive"))
    )
    (net (code "124") (name "PB7_CPU") (class "Default")
      (node (ref "CPU1") (pin "15") (pinfunction "15_15") (pintype "passive"))
    )
    (net (code "125") (name "PB7_GPU") (class "Default")
      (node (ref "GPU1") (pin "15") (pinfunction "15_15") (pintype "passive"))
    )
    (net (code "126") (name "PB8_CPU") (class "Default")
      (node (ref "CPU1") (pin "16") (pinfunction "16_16") (pintype "passive"))
    )
    (net (code "127") (name "PB8_GPU") (class "Default")
      (node (ref "GPU1") (pin "16") (pinfunction "16_16") (pintype "passive"))
    )
    (net (code "128") (name "PB9_CPU") (class "Default")
      (node (ref "CPU1") (pin "17") (pinfunction "17_17") (pintype "passive"))
    )
    (net (code "129") (name "PB9_GPU") (class "Default")
      (node (ref "GPU1") (pin "17") (pinfunction "17_17") (pintype "passive"))
    )
    (net (code "130") (name "PB10_CPU") (class "Default")
      (node (ref "CPU2") (pin "15") (pinfunction "15_15") (pintype "passive"))
    )
    (net (code "131") (name "PB10_GPU") (class "Default")
      (node (ref "GPU2") (pin "15") (pinfunction "15_15") (pintype "passive"))
    )
    (net (code "132") (name "PB11_CPU") (class "Default")
      (node (ref "CPU2") (pin "16") (pinfunction "16_16") (pintype "passive"))
    )
    (net (code "133") (name "PB11_GPU") (class "Default")
      (node (ref "GPU2") (pin "16") (pinfunction "16_16") (pintype "passive"))
    )
    (net (code "134") (name "PB12_CPU") (class "Default")
      (node (ref "CPU1") (pin "1") (pinfunction "1_1") (pintype "passive"))
    )
    (net (code "135") (name "PB12_GPU") (class "Default")
      (node (ref "GPU1") (pin "1") (pinfunction "1_1") (pintype "passive"))
    )
    (net (code "136") (name "PB13_CPU") (class "Default")
      (node (ref "CPU1") (pin "2") (pinfunction "2_2") (pintype "passive"))
    )
    (net (code "137") (name "PB13_GPU") (class "Default")
      (node (ref "GPU1") (pin "2") (pinfunction "2_2") (pintype "passive"))
    )
    (net (code "138") (name "PB14_CPU") (class "Default")
      (node (ref "CPU1") (pin "3") (pinfunction "3_3") (pintype "passive"))
    )
    (net (code "139") (name "PB14_GPU") (class "Default")
      (node (ref "GPU1") (pin "3") (pinfunction "3_3") (pintype "passive"))
    )
    (net (code "140") (name "PB15_CPU") (class "Default")
      (node (ref "CPU1") (pin "4") (pinfunction "4_4") (pintype "passive"))
    )
    (net (code "141") (name "PB15_GPU") (class "Default")
      (node (ref "GPU1") (pin "4") (pinfunction "4_4") (pintype "passive"))
    )
    (net (code "142") (name "PC13_CPU") (class "Default")
      (node (ref "CPU2") (pin "2") (pinfunction "2_2") (pintype "passive"))
    )
    (net (code "143") (name "PC13_GPU") (class "Default")
      (node (ref "GPU2") (pin "2") (pinfunction "2_2") (pintype "passive"))
    )
    (net (code "144") (name "PC14_CPU") (class "Default")
      (node (ref "CPU2") (pin "3") (pinfunction "3_3") (pintype "passive"))
    )
    (net (code "145") (name "PC14_GPU") (class "Default")
      (node (ref "GPU2") (pin "3") (pinfunction "3_3") (pintype "passive"))
    )
    (net (code "146") (name "PC15_CPU") (class "Default")
      (node (ref "CPU2") (pin "4") (pinfunction "4_4") (pintype "passive"))
    )
    (net (code "147") (name "PC15_GPU") (class "Default")
      (node (ref "GPU2") (pin "4") (pinfunction "4_4") (pintype "passive"))
    )
    (net (code "148") (name "RED_LSP") (class "Default")
      (node (ref "R6") (pin "1") (pinfunction "1_1") (pintype "passive"))
    )
    (net (code "149") (name "RED_MMSP") (class "Default")
      (node (ref "R8") (pin "1") (pinfunction "1_1") (pintype "passive"))
    )
    (net (code "150") (name "RED_MSP") (class "Default")
      (node (ref "R9") (pin "1") (pinfunction "1_1") (pintype "passive"))
    )
    (net (code "151") (name "SYNC") (class "Default")
      (node (ref "JP1") (pin "3") (pinfunction "3_3") (pintype "passive"))
      (node (ref "R22") (pin "1") (pinfunction "1_1") (pintype "passive"))
    )
    (net (code "152") (name "VBAT_CPU") (class "Default")
      (node (ref "CPU2") (pin "1") (pinfunction "1_1") (pintype "passive"))
    )
    (net (code "153") (name "VBAT_GPU") (class "Default")
      (node (ref "GPU2") (pin "1") (pinfunction "1_1") (pintype "passive"))
    )
    (net (code "154") (name "VGA_BLUE") (class "Default")
      (node (ref "J7") (pin "2") (pinfunction "2_2") (pintype "bidirectional"))
      (node (ref "R17") (pin "2") (pinfunction "2_2") (pintype "passive"))
      (node (ref "R18") (pin "2") (pinfunction "2_2") (pintype "passive"))
      (node (ref "R19") (pin "2") (pinfunction "2_2") (pintype "passive"))
      (node (ref "R20") (pin "2") (pinfunction "2_2") (pintype "passive"))
    )
    (net (code "155") (name "VGA_GREEN") (class "Default")
      (node (ref "J7") (pin "3") (pinfunction "3_3") (pintype "bidirectional"))
      (node (ref "R12") (pin "2") (pinfunction "2_2") (pintype "passive"))
      (node (ref "R13") (pin "2") (pinfunction "2_2") (pintype "passive"))
      (node (ref "R14") (pin "2") (pinfunction "2_2") (pintype "passive"))
      (node (ref "R15") (pin "2") (pinfunction "2_2") (pintype "passive"))
    )
    (net (code "156") (name "VGA_RED") (class "Default")
      (node (ref "J7") (pin "1") (pinfunction "1_1") (pintype "bidirectional"))
      (node (ref "R10") (pin "2") (pinfunction "2_2") (pintype "passive"))
      (node (ref "R7") (pin "2") (pinfunction "2_2") (pintype "passive"))
      (node (ref "R8") (pin "2") (pinfunction "2_2") (pintype "passive"))
      (node (ref "R9") (pin "2") (pinfunction "2_2") (pintype "passive"))
    )
    (net (code "157") (name "VSYNC") (class "Default")
      (node (ref "J7") (pin "14") (pinfunction "14_14") (pintype "bidirectional"))
    )
    (net (code "158") (name "unconnected-(IC1A-W-Pad6)") (class "Default")
      (node (ref "IC1") (pin "6") (pinfunction "W_6") (pintype "output"))
    )
    (net (code "159") (name "unconnected-(IC2A-W-Pad6)") (class "Default")
      (node (ref "IC2") (pin "6") (pinfunction "W_6") (pintype "output"))
    )
    (net (code "160") (name "unconnected-(IC3A-W-Pad6)") (class "Default")
      (node (ref "IC3") (pin "6") (pinfunction "W_6") (pintype "output"))
    )
    (net (code "161") (name "unconnected-(IC4A-W-Pad6)") (class "Default")
      (node (ref "IC4") (pin "6") (pinfunction "W_6") (pintype "output"))
    )
    (net (code "162") (name "unconnected-(IC5A-Y-Pad5)") (class "Default")
      (node (ref "IC5") (pin "5") (pinfunction "Y_5") (pintype "output"))
    )
    (net (code "163") (name "unconnected-(IC6A-Y-Pad5)") (class "Default")
      (node (ref "IC6") (pin "5") (pinfunction "Y_5") (pintype "output"))
    )
    (net (code "164") (name "unconnected-(IC7A-QF-Pad5)") (class "Default")
      (node (ref "IC7") (pin "5") (pinfunction "QF_5") (pintype "tri_state"))
    )
    (net (code "165") (name "unconnected-(IC7A-QG-Pad6)") (class "Default")
      (node (ref "IC7") (pin "6") (pinfunction "QG_6") (pintype "tri_state"))
    )
    (net (code "166") (name "unconnected-(IC7A-QH-Pad7)") (class "Default")
      (node (ref "IC7") (pin "7") (pinfunction "QH_7") (pintype "tri_state"))
    )
    (net (code "167") (name "unconnected-(IC7A-RCO-Pad9)") (class "Default")
      (node (ref "IC7") (pin "9") (pinfunction "RCO_9") (pintype "output"))
    )
    (net (code "168") (name "unconnected-(IC8B-O-Pad4)") (class "Default")
      (node (ref "IC8") (pin "4") (pinfunction "O_4") (pintype "output"))
    )
    (net (code "169") (name "unconnected-(IC8C-O-Pad10)") (class "Default")
      (node (ref "IC8") (pin "10") (pinfunction "O_10") (pintype "output"))
    )
    (net (code "170") (name "unconnected-(IC8D-O-Pad13)") (class "Default")
      (node (ref "IC8") (pin "13") (pinfunction "O_13") (pintype "output"))
    )
    (net (code "171") (name "unconnected-(J5-CC-PadA5)") (class "Default")
      (node (ref "J5") (pin "A5") (pinfunction "CC_A5") (pintype "passive"))
    )
    (net (code "172") (name "unconnected-(J5-DN1-PadA7)") (class "Default")
      (node (ref "J5") (pin "A7") (pinfunction "DN1_A7") (pintype "passive"))
    )
    (net (code "173") (name "unconnected-(J5-DP1-PadA6)") (class "Default")
      (node (ref "J5") (pin "A6") (pinfunction "DP1_A6") (pintype "passive"))
    )
    (net (code "174") (name "unconnected-(J5-SBU1-PadA8)") (class "Default")
      (node (ref "J5") (pin "A8") (pinfunction "SBU1_A8") (pintype "passive"))
    )
    (net (code "175") (name "unconnected-(J5-SSRXN2-PadA10)") (class "Default")
      (node (ref "J5") (pin "A10") (pinfunction "SSRXN2_A10") (pintype "passive"))
    )
    (net (code "176") (name "unconnected-(J5-SSRXP2-PadA11)") (class "Default")
      (node (ref "J5") (pin "A11") (pinfunction "SSRXP2_A11") (pintype "passive"))
    )
    (net (code "177") (name "unconnected-(J5-SSTXN1-PadA3)") (class "Default")
      (node (ref "J5") (pin "A3") (pinfunction "SSTXN1_A3") (pintype "passive"))
    )
    (net (code "178") (name "unconnected-(J5-SSTXP1-PadA2)") (class "Default")
      (node (ref "J5") (pin "A2") (pinfunction "SSTXP1_A2") (pintype "passive"))
    )
    (net (code "179") (name "unconnected-(J6-LEFT-PadSHIELD)") (class "Default")
      (node (ref "J6") (pin "SHIELD") (pinfunction "LEFT_SHIELD") (pintype "bidirectional"))
    )
    (net (code "180") (name "unconnected-(J6-RIGHT-PadTIP)") (class "Default")
      (node (ref "J6") (pin "TIP") (pinfunction "RIGHT_TIP") (pintype "bidirectional"))
    )
    (net (code "181") (name "unconnected-(J6-SLEEVE-PadRING1)") (class "Default")
      (node (ref "J6") (pin "RING1") (pinfunction "SLEEVE_RING1") (pintype "bidirectional"))
    )
    (net (code "182") (name "unconnected-(J7-Pad4)") (class "Default")
      (node (ref "J7") (pin "4") (pinfunction "4_4") (pintype "bidirectional"))
    )
    (net (code "183") (name "unconnected-(J7-Pad9)") (class "Default")
      (node (ref "J7") (pin "9") (pinfunction "9_9") (pintype "bidirectional"))
    )
    (net (code "184") (name "unconnected-(J7-Pad11)") (class "Default")
      (node (ref "J7") (pin "11") (pinfunction "11_11") (pintype "bidirectional"))
    )
    (net (code "185") (name "unconnected-(J7-Pad12)") (class "Default")
      (node (ref "J7") (pin "12") (pinfunction "12_12") (pintype "bidirectional"))
    )
    (net (code "186") (name "unconnected-(J7-Pad15)") (class "Default")
      (node (ref "J7") (pin "15") (pinfunction "15_15") (pintype "bidirectional"))
    )
    (net (code "187") (name "unconnected-(J7-PadMH1)") (class "Default")
      (node (ref "J7") (pin "MH1") (pinfunction "MH1_MH1") (pintype "bidirectional"))
    )
    (net (code "188") (name "unconnected-(J7-PadMH2)") (class "Default")
      (node (ref "J7") (pin "MH2") (pinfunction "MH2_MH2") (pintype "bidirectional"))
    )
    (net (code "189") (name "unconnected-(U$1-PadP$1)") (class "Default")
      (node (ref "U$1") (pin "P$1") (pinfunction "P$1_P$1") (pintype "bidirectional"))
    )
    (net (code "190") (name "unconnected-(U$1-PadP$2)") (class "Default")
      (node (ref "U$1") (pin "P$2") (pinfunction "P$2_P$2") (pintype "bidirectional"))
    )
    (net (code "191") (name "unconnected-(U$1-PadP$3)") (class "Default")
      (node (ref "U$1") (pin "P$3") (pinfunction "P$3_P$3") (pintype "bidirectional"))
    )
    (net (code "192") (name "unconnected-(U$1-PadP$4)") (class "Default")
      (node (ref "U$1") (pin "P$4") (pinfunction "P$4_P$4") (pintype "bidirectional"))
    )
    (net (code "193") (name "unconnected-(U$1-PadP$5)") (class "Default")
      (node (ref "U$1") (pin "P$5") (pinfunction "P$5_P$5") (pintype "bidirectional"))
    )
    (net (code "194") (name "unconnected-(U$1-PadP$6)") (class "Default")
      (node (ref "U$1") (pin "P$6") (pinfunction "P$6_P$6") (pintype "bidirectional"))
    )
    (net (code "195") (name "unconnected-(U$1-PadP$7)") (class "Default")
      (node (ref "U$1") (pin "P$7") (pinfunction "P$7_P$7") (pintype "bidirectional"))
    )
    (net (code "196") (name "unconnected-(U$1-PadP$8)") (class "Default")
      (node (ref "U$1") (pin "P$8") (pinfunction "P$8_P$8") (pintype "bidirectional"))
    )
    (net (code "197") (name "unconnected-(U$1-PadP$9)") (class "Default")
      (node (ref "U$1") (pin "P$9") (pinfunction "P$9_P$9") (pintype "bidirectional"))
    )
    (net (code "198") (name "unconnected-(U$1-PadP$10)") (class "Default")
      (node (ref "U$1") (pin "P$10") (pinfunction "P$10_P$10") (pintype "bidirectional"))
    )
    (net (code "199") (name "unconnected-(U$1-PadP$11)") (class "Default")
      (node (ref "U$1") (pin "P$11") (pinfunction "P$11_P$11") (pintype "bidirectional"))
    )
    (net (code "200") (name "unconnected-(U$1-PadP$12)") (class "Default")
      (node (ref "U$1") (pin "P$12") (pinfunction "P$12_P$12") (pintype "bidirectional"))
    )
    (net (code "201") (name "unconnected-(U$1-PadP$13)") (class "Default")
      (node (ref "U$1") (pin "P$13") (pinfunction "P$13_P$13") (pintype "bidirectional"))
    )
    (net (code "202") (name "unconnected-(U$1-PadP$14)") (class "Default")
      (node (ref "U$1") (pin "P$14") (pinfunction "P$14_P$14") (pintype "bidirectional"))
    )
    (net (code "203") (name "unconnected-(U$1-PadP$15)") (class "Default")
      (node (ref "U$1") (pin "P$15") (pinfunction "P$15_P$15") (pintype "bidirectional"))
    )
    (net (code "204") (name "unconnected-(U$1-PadP$16)") (class "Default")
      (node (ref "U$1") (pin "P$16") (pinfunction "P$16_P$16") (pintype "bidirectional"))
    )
    (net (code "205") (name "unconnected-(U$1-PadP$17)") (class "Default")
      (node (ref "U$1") (pin "P$17") (pinfunction "P$17_P$17") (pintype "bidirectional"))
    )
    (net (code "206") (name "unconnected-(U$1-PadP$18)") (class "Default")
      (node (ref "U$1") (pin "P$18") (pinfunction "P$18_P$18") (pintype "bidirectional"))
    )
    (net (code "207") (name "unconnected-(U$1-PadP$19)") (class "Default")
      (node (ref "U$1") (pin "P$19") (pinfunction "P$19_P$19") (pintype "bidirectional"))
    )
    (net (code "208") (name "unconnected-(U$1-PadP$20)") (class "Default")
      (node (ref "U$1") (pin "P$20") (pinfunction "P$20_P$20") (pintype "bidirectional"))
    )
  )
)
